# vdg_voltage_sensor_rev2.net
KiCad netlist of a schematic drawn in EAGLE
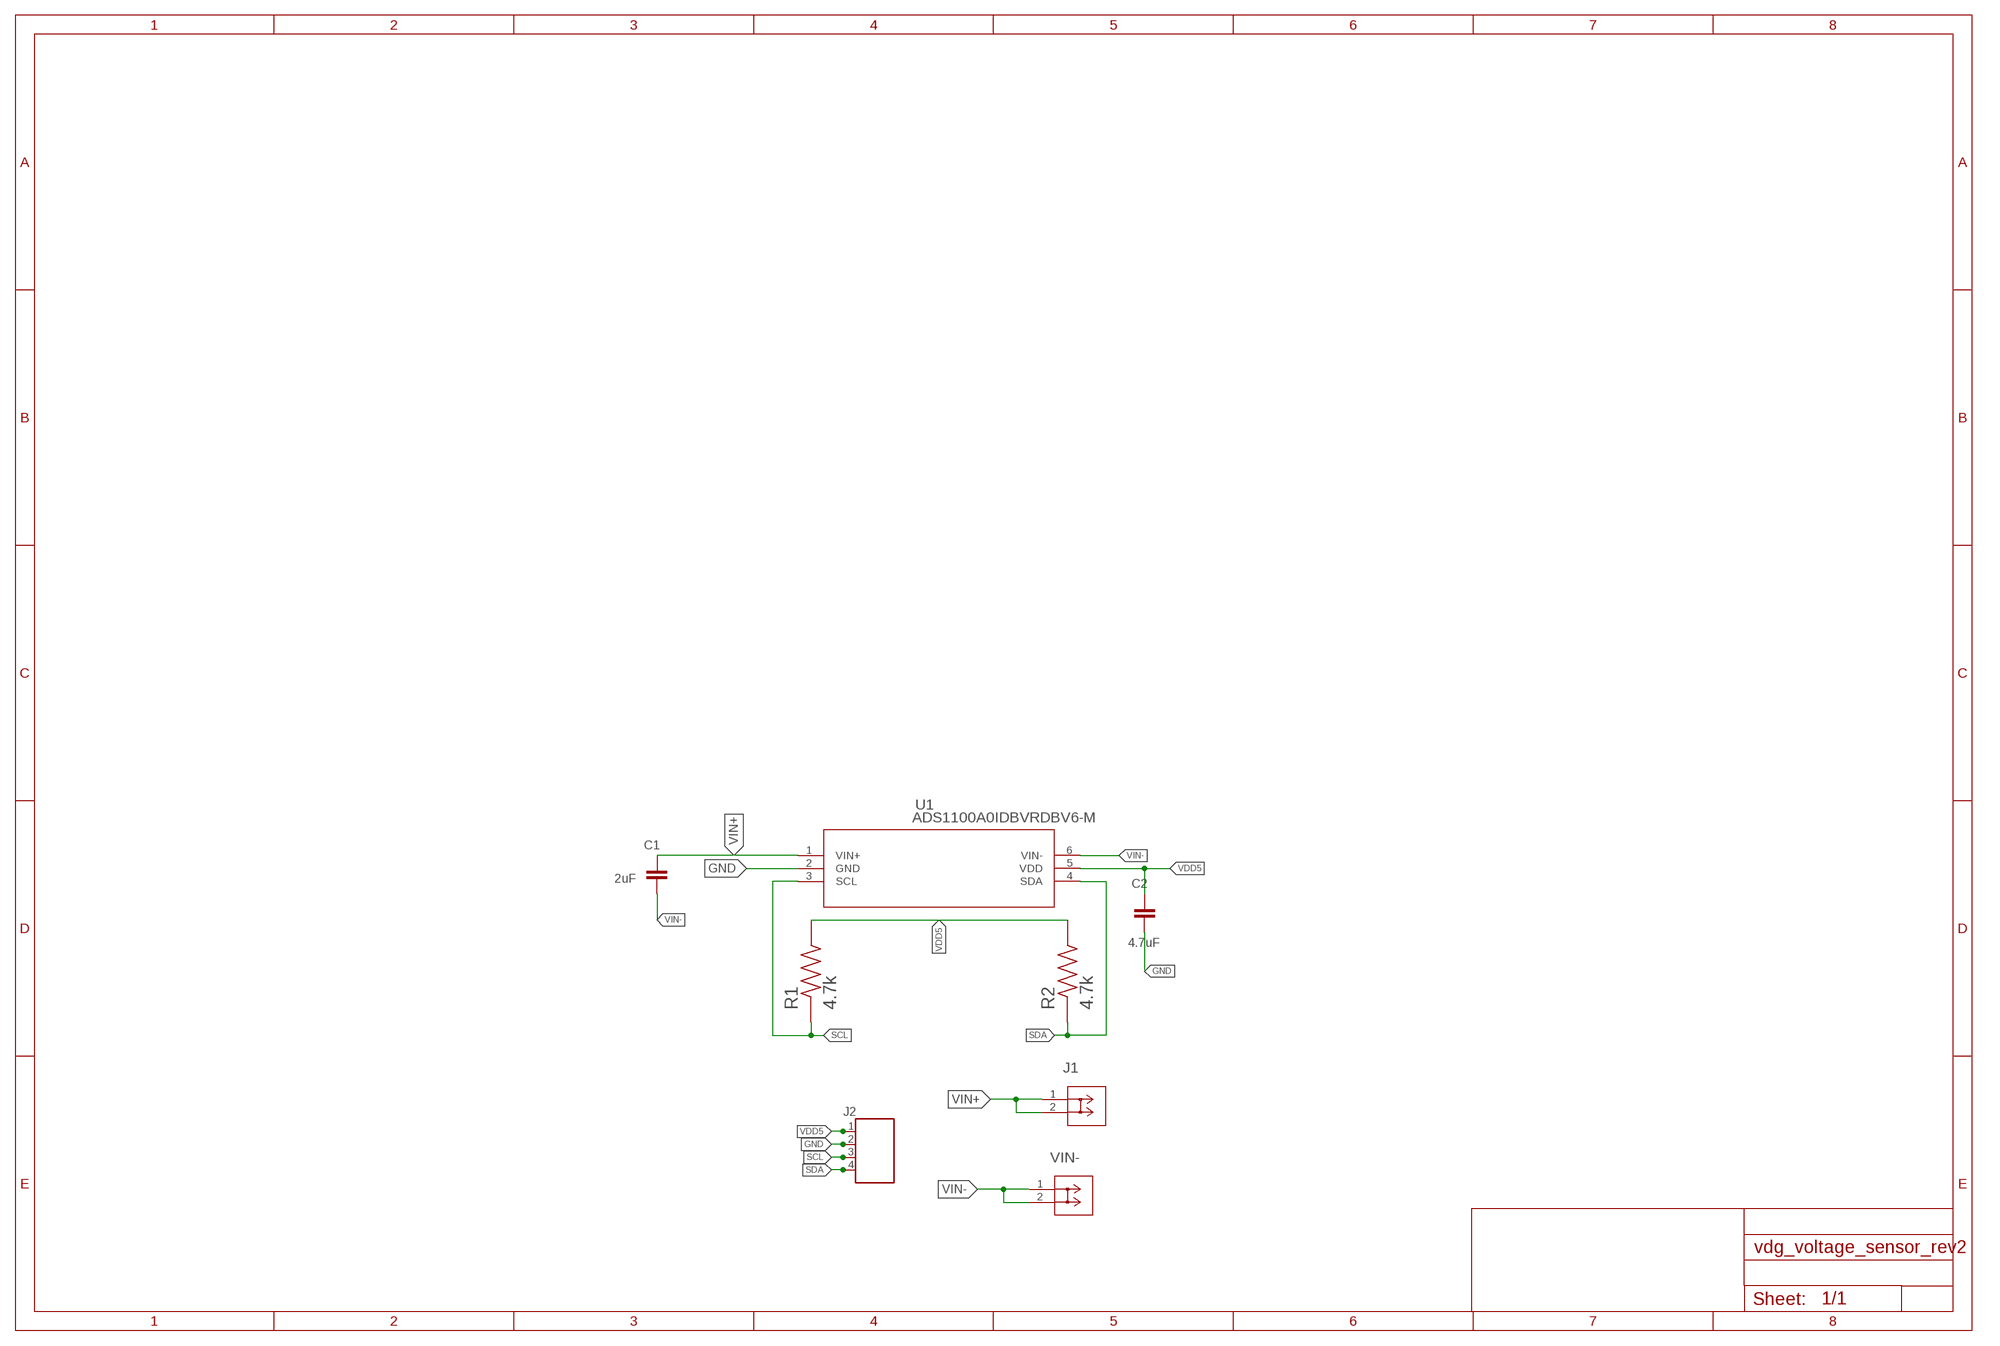
[diagram p0: schematic, sheet 1]

(export (version "E")
  (design (tool "Eeschema 10.0.6"))
  (components
    (comp (ref "C1")
      (value "2uF")
      (footprint "eagle-import:CAP_1206")
      (fields
        (field (name "DIGIKEY_PART_NUMBER") "GRM31CR60J107ME39L")
        (field (name "MANUFACTURER") "Murata Electronics North America")
        (field (name "CREATED_BY") "PCBLayout.com")
      )
      (libsource (lib "eagle-import") (part "GRM31CR60J107ME39L"))
    )
    (comp (ref "C2")
      (value "4.7uF")
      (footprint "eagle-import:CAP_1206")
      (fields
        (field (name "DIGIKEY_PART_NUMBER") "GRM31CR60J107ME39L")
        (field (name "MANUFACTURER") "Murata Electronics North America")
        (field (name "CREATED_BY") "PCBLayout.com")
      )
      (libsource (lib "eagle-import") (part "GRM31CR60J107ME39L"))
    )
    (comp (ref "J1")
      (value "VANDEGRAAFF")
      (footprint "eagle-import:SR99S01VBNN00G7_MZC")
      (fields
        (field (name "MANUFACTURER_PART_NUMBER") "SR99S01VBNN00G7")
        (field (name "COPYRIGHT") "Copyright (C) 2018 Accelerated Designs. All rights reserved")
      )
      (libsource (lib "eagle-import") (part "SR99S01VBNN00G7"))
    )
    (comp (ref "J2")
      (value "691131710004")
      (footprint "eagle-import:691131710004")
      (libsource (lib "eagle-import") (part "691131710004"))
    )
    (comp (ref "R1")
      (value "4.7k")
      (footprint "eagle-import:RESC3115X65N")
      (fields
        (field (name "COMMENT") "1-2176328-4")
        (field (name "MF") "TE Connectivity")
        (field (name "MP") "CRGP1206F120R")
      )
      (libsource (lib "eagle-import") (part "CRGP1206F120R"))
    )
    (comp (ref "R2")
      (value "4.7k")
      (footprint "eagle-import:RESC3115X65N")
      (fields
        (field (name "COMMENT") "1-2176328-4")
        (field (name "MF") "TE Connectivity")
        (field (name "MP") "CRGP1206F120R")
      )
      (libsource (lib "eagle-import") (part "CRGP1206F120R"))
    )
    (comp (ref "U1")
      (value "ADS1100A0IDBVRDBV6-M")
      (footprint "eagle-import:DBV6-M")
      (fields
        (field (name "GENERIC_PART_NUMBER") "ADS1100")
        (field (name "MANUFACTURER") "Texas Instruments")
      )
      (libsource (lib "eagle-import") (part "ADS1100A0IDBVRDBV6-M"))
    )
    (comp (ref "VIN-")
      (value "SR99S01VBNN00G7")
      (footprint "eagle-import:SR99S01VBNN00G7_MZC")
      (fields (field (name "COPYRIGHT") "Copyright (C) 2018 Accelerated Designs. All rights reserved"))
      (libsource (lib "eagle-import") (part "SR99S01VBNN00G7"))
    )
  )
  (nets
    (net (code "1") (name "GND") (class "Default")
      (node (ref "C2") (pin "2") (pinfunction "2_2") (pintype "passive"))
      (node (ref "J2") (pin "2") (pinfunction "2_2") (pintype "passive"))
      (node (ref "U1") (pin "2") (pinfunction "GND_2") (pintype "power_in"))
    )
    (net (code "2") (name "SCL") (class "Default")
      (node (ref "J2") (pin "3") (pinfunction "3_3") (pintype "passive"))
      (node (ref "R1") (pin "1") (pinfunction "1_1") (pintype "passive"))
      (node (ref "U1") (pin "3") (pinfunction "SCL_3") (pintype "passive"))
    )
    (net (code "3") (name "SDA") (class "Default")
      (node (ref "J2") (pin "4") (pinfunction "4_4") (pintype "passive"))
      (node (ref "R2") (pin "1") (pinfunction "1_1") (pintype "passive"))
      (node (ref "U1") (pin "4") (pinfunction "SDA_4") (pintype "passive"))
    )
    (net (code "4") (name "VDD5") (class "Default")
      (node (ref "C2") (pin "1") (pinfunction "1_1") (pintype "passive"))
      (node (ref "J2") (pin "1") (pinfunction "1_1") (pintype "passive"))
      (node (ref "R1") (pin "2") (pinfunction "2_2") (pintype "passive"))
      (node (ref "R2") (pin "2") (pinfunction "2_2") (pintype "passive"))
      (node (ref "U1") (pin "5") (pinfunction "VDD_5") (pintype "power_in"))
    )
    (net (code "5") (name "VIN+") (class "Default")
      (node (ref "C1") (pin "1") (pinfunction "1_1") (pintype "passive"))
      (node (ref "J1") (pin "1") (pinfunction "1_1") (pintype "passive"))
      (node (ref "J1") (pin "2") (pinfunction "2_2") (pintype "passive"))
      (node (ref "U1") (pin "1") (pinfunction "VIN+_1") (pintype "input"))
    )
    (net (code "6") (name "VIN-") (class "Default")
      (node (ref "C1") (pin "2") (pinfunction "2_2") (pintype "passive"))
      (node (ref "U1") (pin "6") (pinfunction "VIN-_6") (pintype "input"))
      (node (ref "VIN-") (pin "1") (pinfunction "1_1") (pintype "passive"))
      (node (ref "VIN-") (pin "2") (pinfunction "2_2") (pintype "passive"))
    )
  )
)
